# Arduino_Headers.net
KiCad netlist of a schematic drawn in Altium Designer
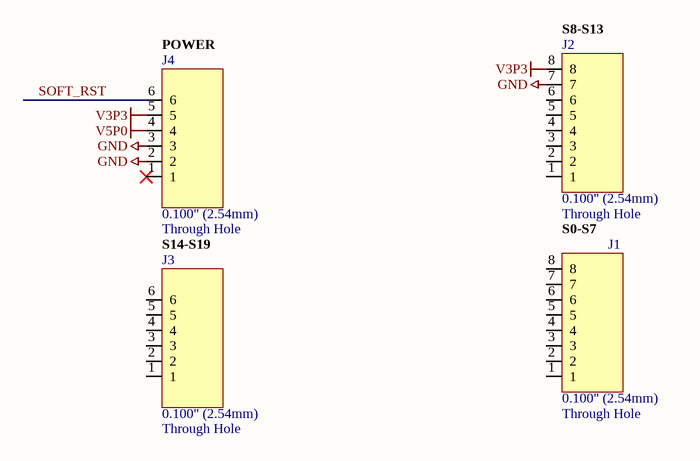
[diagram p0: Arduino Headers.SchDoc]

(export (version "E")
  (design (tool "Eeschema 10.0.6"))
  (components
    (comp (ref "J1")
      (value "J_HDR1X8_THRHOLE_VERT")
      (footprint "HDR_1X8")
      (description "CONN HEADER .100\" 12POS TIN PCB")
      (fields
        (field (name "MANUFACTURER") "Samtec")
        (field (name "MANUFACTURER PART NUMBER") "TS-108-T-A")
        (field (name "PITCH") "0.100\" (2.54mm)")
        (field (name "MOUNTING TYPE") "Through Hole")
      )
      (libsource (lib "Main Library") (part "J_HDR1X8_THRHOLE_VERT"))
    )
    (comp (ref "J2")
      (value "J_HDR1X8_THRHOLE_VERT")
      (footprint "HDR_1X8")
      (description "CONN HEADER .100\" 12POS TIN PCB")
      (fields
        (field (name "MANUFACTURER") "Samtec")
        (field (name "MANUFACTURER PART NUMBER") "TS-108-T-A")
        (field (name "PITCH") "0.100\" (2.54mm)")
        (field (name "MOUNTING TYPE") "Through Hole")
      )
      (libsource (lib "Main Library") (part "J_HDR1X8_THRHOLE_VERT"))
    )
    (comp (ref "J3")
      (value "J_HDR1X6_THRHOLE_VERT")
      (footprint "HDR_1X6")
      (description "CONN HEADER .100\" 12POS TIN PCB")
      (fields
        (field (name "MANUFACTURER") "Samtec")
        (field (name "MANUFACTURER PART NUMBER") "TSW-106-07-T-S")
        (field (name "PITCH") "0.100\" (2.54mm)")
        (field (name "MOUNTING TYPE") "Through Hole")
      )
      (libsource (lib "Main Library") (part "J_HDR1X6_THRHOLE_VERT"))
    )
    (comp (ref "J4")
      (value "J_HDR1X6_THRHOLE_VERT")
      (footprint "HDR_1X6")
      (description "CONN HEADER .100\" 12POS TIN PCB")
      (fields
        (field (name "MANUFACTURER") "Samtec")
        (field (name "MANUFACTURER PART NUMBER") "TSW-106-07-T-S")
        (field (name "PITCH") "0.100\" (2.54mm)")
        (field (name "MOUNTING TYPE") "Through Hole")
      )
      (libsource (lib "Main Library") (part "J_HDR1X6_THRHOLE_VERT"))
    )
  )
  (nets
    (net (code "1") (name "/SOFT_RST") (class "Default")
      (node (ref "J4") (pin "6") (pinfunction "6_6") (pintype "passive"))
    )
    (net (code "2") (name "GND") (class "Default")
      (node (ref "J2") (pin "7") (pinfunction "7_7") (pintype "passive"))
      (node (ref "J4") (pin "2") (pinfunction "2_2") (pintype "passive"))
      (node (ref "J4") (pin "3") (pinfunction "3_3") (pintype "passive"))
    )
    (net (code "3") (name "V3P3") (class "Default")
      (node (ref "J2") (pin "8") (pinfunction "8_8") (pintype "passive"))
      (node (ref "J4") (pin "5") (pinfunction "5_5") (pintype "passive"))
    )
    (net (code "4") (name "V5P0") (class "Default")
      (node (ref "J4") (pin "4") (pinfunction "4_4") (pintype "passive"))
    )
    (net (code "5") (name "unconnected-(J1-Pad1)") (class "Default")
      (node (ref "J1") (pin "1") (pinfunction "1_1") (pintype "passive"))
    )
    (net (code "6") (name "unconnected-(J1-Pad2)") (class "Default")
      (node (ref "J1") (pin "2") (pinfunction "2_2") (pintype "passive"))
    )
    (net (code "7") (name "unconnected-(J1-Pad3)") (class "Default")
      (node (ref "J1") (pin "3") (pinfunction "3_3") (pintype "passive"))
    )
    (net (code "8") (name "unconnected-(J1-Pad4)") (class "Default")
      (node (ref "J1") (pin "4") (pinfunction "4_4") (pintype "passive"))
    )
    (net (code "9") (name "unconnected-(J1-Pad5)") (class "Default")
      (node (ref "J1") (pin "5") (pinfunction "5_5") (pintype "passive"))
    )
    (net (code "10") (name "unconnected-(J1-Pad6)") (class "Default")
      (node (ref "J1") (pin "6") (pinfunction "6_6") (pintype "passive"))
    )
    (net (code "11") (name "unconnected-(J1-Pad7)") (class "Default")
      (node (ref "J1") (pin "7") (pinfunction "7_7") (pintype "passive"))
    )
    (net (code "12") (name "unconnected-(J1-Pad8)") (class "Default")
      (node (ref "J1") (pin "8") (pinfunction "8_8") (pintype "passive"))
    )
    (net (code "13") (name "unconnected-(J2-Pad1)") (class "Default")
      (node (ref "J2") (pin "1") (pinfunction "1_1") (pintype "passive"))
    )
    (net (code "14") (name "unconnected-(J2-Pad2)") (class "Default")
      (node (ref "J2") (pin "2") (pinfunction "2_2") (pintype "passive"))
    )
    (net (code "15") (name "unconnected-(J2-Pad3)") (class "Default")
      (node (ref "J2") (pin "3") (pinfunction "3_3") (pintype "passive"))
    )
    (net (code "16") (name "unconnected-(J2-Pad4)") (class "Default")
      (node (ref "J2") (pin "4") (pinfunction "4_4") (pintype "passive"))
    )
    (net (code "17") (name "unconnected-(J2-Pad5)") (class "Default")
      (node (ref "J2") (pin "5") (pinfunction "5_5") (pintype "passive"))
    )
    (net (code "18") (name "unconnected-(J2-Pad6)") (class "Default")
      (node (ref "J2") (pin "6") (pinfunction "6_6") (pintype "passive"))
    )
    (net (code "19") (name "unconnected-(J3-Pad1)") (class "Default")
      (node (ref "J3") (pin "1") (pinfunction "1_1") (pintype "passive"))
    )
    (net (code "20") (name "unconnected-(J3-Pad2)") (class "Default")
      (node (ref "J3") (pin "2") (pinfunction "2_2") (pintype "passive"))
    )
    (net (code "21") (name "unconnected-(J3-Pad3)") (class "Default")
      (node (ref "J3") (pin "3") (pinfunction "3_3") (pintype "passive"))
    )
    (net (code "22") (name "unconnected-(J3-Pad4)") (class "Default")
      (node (ref "J3") (pin "4") (pinfunction "4_4") (pintype "passive"))
    )
    (net (code "23") (name "unconnected-(J3-Pad5)") (class "Default")
      (node (ref "J3") (pin "5") (pinfunction "5_5") (pintype "passive"))
    )
    (net (code "24") (name "unconnected-(J3-Pad6)") (class "Default")
      (node (ref "J3") (pin "6") (pinfunction "6_6") (pintype "passive"))
    )
    (net (code "25") (name "unconnected-(J4-Pad1)") (class "Default")
      (node (ref "J4") (pin "1") (pinfunction "1_1") (pintype "passive+no_connect"))
    )
  )
)
